# Nodino-Core2538.net
KiCad netlist of a schematic drawn in EAGLE
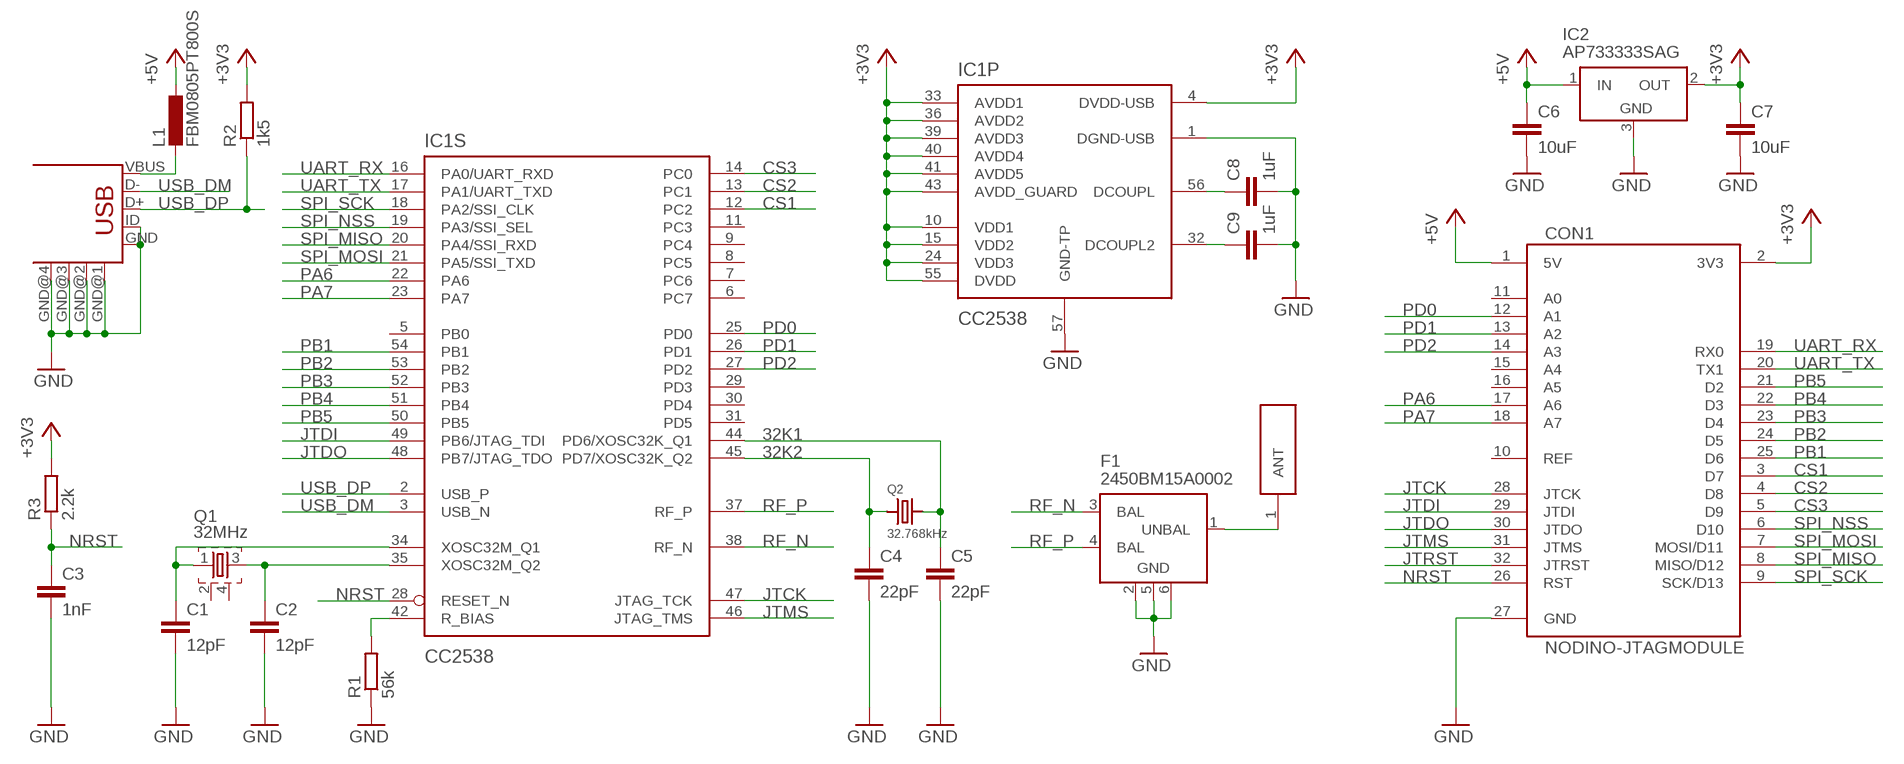
[diagram p0: schematic, sheet 1]

(export (version "E")
  (design (tool "Eeschema 10.0.6"))
  (components
    (comp (ref "ANT1")
      (value "2450AT18B100")
      (footprint "eagle-import:2450AT18B100")
      (libsource (lib "eagle-import") (part "2450AT18B100"))
    )
    (comp (ref "C1")
      (value "12pF")
      (footprint "eagle-import:C0603K")
      (libsource (lib "eagle-import") (part "C-EUC0603K"))
    )
    (comp (ref "C2")
      (value "12pF")
      (footprint "eagle-import:C0603K")
      (libsource (lib "eagle-import") (part "C-EUC0603K"))
    )
    (comp (ref "C3")
      (value "1nF")
      (footprint "eagle-import:C0603K")
      (libsource (lib "eagle-import") (part "C-EUC0603K"))
    )
    (comp (ref "C4")
      (value "22pF")
      (footprint "eagle-import:C0603K")
      (libsource (lib "eagle-import") (part "C-EUC0603K"))
    )
    (comp (ref "C5")
      (value "22pF")
      (footprint "eagle-import:C0603K")
      (libsource (lib "eagle-import") (part "C-EUC0603K"))
    )
    (comp (ref "C6")
      (value "10uF")
      (footprint "eagle-import:C0603K")
      (libsource (lib "eagle-import") (part "C-EUC0603K"))
    )
    (comp (ref "C7")
      (value "10uF")
      (footprint "eagle-import:C0603K")
      (libsource (lib "eagle-import") (part "C-EUC0603K"))
    )
    (comp (ref "C8")
      (value "1uF")
      (footprint "eagle-import:C0603K")
      (libsource (lib "eagle-import") (part "C-EUC0603K"))
    )
    (comp (ref "C9")
      (value "1uF")
      (footprint "eagle-import:C0603K")
      (libsource (lib "eagle-import") (part "C-EUC0603K"))
    )
    (comp (ref "CON1")
      (value "NODINO-JTAGMODULE")
      (footprint "eagle-import:NODINO-JTAG-MOD")
      (libsource (lib "eagle-import") (part "NODINO-JTAGMODULE"))
    )
    (comp (ref "CON2")
      (value "USB-OTG_SHIELD")
      (footprint "eagle-import:USB-UAB-S1")
      (libsource (lib "eagle-import") (part "USB-OTG_SHIELD"))
    )
    (comp (ref "F1")
      (value "2450BM15A0002")
      (footprint "eagle-import:2450BM15A0002")
      (libsource (lib "eagle-import") (part "2450BM15A0002"))
    )
    (comp (ref "IC1")
      (value "CC2538")
      (footprint "eagle-import:QFN56P800X800X100-57N")
      (libsource (lib "eagle-import") (part "CC2538"))
    )
    (comp (ref "IC2")
      (value "AP733333SAG")
      (footprint "eagle-import:SOT23")
      (libsource (lib "eagle-import") (part "AP733333SAG"))
    )
    (comp (ref "L1")
      (value "FBM0805PT800S")
      (footprint "eagle-import:L0805")
      (libsource (lib "eagle-import") (part "L-EUL0805"))
    )
    (comp (ref "Q1")
      (value "32MHz")
      (footprint "eagle-import:FA-20H")
      (libsource (lib "eagle-import") (part "FA-20H"))
    )
    (comp (ref "Q2")
      (value "32.768kHz")
      (footprint "eagle-import:ABS07")
      (libsource (lib "eagle-import") (part "CRYSTAL.ABS07"))
    )
    (comp (ref "R1")
      (value "56k")
      (footprint "eagle-import:R0603K")
      (libsource (lib "eagle-import") (part "R-EU_R0603K"))
    )
    (comp (ref "R2")
      (value "1k5")
      (footprint "eagle-import:R0603K")
      (libsource (lib "eagle-import") (part "R-EU_R0603K"))
    )
    (comp (ref "R3")
      (value "2.2k")
      (footprint "eagle-import:R0603K")
      (libsource (lib "eagle-import") (part "R-EU_R0603K"))
    )
  )
  (nets
    (net (code "1") (name "+3V3") (class "Default")
      (node (ref "C7") (pin "1") (pinfunction "1_1") (pintype "passive"))
      (node (ref "CON1") (pin "2") (pinfunction "3V3_2") (pintype "bidirectional"))
      (node (ref "IC1") (pin "10") (pinfunction "VDD1_10") (pintype "power_in"))
      (node (ref "IC1") (pin "15") (pinfunction "VDD2_15") (pintype "power_in"))
      (node (ref "IC1") (pin "24") (pinfunction "VDD3_24") (pintype "power_in"))
      (node (ref "IC1") (pin "33") (pinfunction "AVDD1_33") (pintype "power_in"))
      (node (ref "IC1") (pin "36") (pinfunction "AVDD2_36") (pintype "power_in"))
      (node (ref "IC1") (pin "39") (pinfunction "AVDD3_39") (pintype "power_in"))
      (node (ref "IC1") (pin "4") (pinfunction "DVDD-USB_4") (pintype "power_in"))
      (node (ref "IC1") (pin "40") (pinfunction "AVDD4_40") (pintype "power_in"))
      (node (ref "IC1") (pin "41") (pinfunction "AVDD5_41") (pintype "power_in"))
      (node (ref "IC1") (pin "43") (pinfunction "AVDD_GUARD_43") (pintype "power_in"))
      (node (ref "IC1") (pin "55") (pinfunction "DVDD_55") (pintype "power_in"))
      (node (ref "IC2") (pin "2") (pinfunction "OUT_2") (pintype "output"))
      (node (ref "R2") (pin "2") (pinfunction "2_2") (pintype "passive"))
      (node (ref "R3") (pin "2") (pinfunction "2_2") (pintype "passive"))
    )
    (net (code "2") (name "+5V") (class "Default")
      (node (ref "C6") (pin "1") (pinfunction "1_1") (pintype "passive"))
      (node (ref "CON1") (pin "1") (pinfunction "5V_1") (pintype "bidirectional"))
      (node (ref "IC2") (pin "1") (pinfunction "IN_1") (pintype "input"))
      (node (ref "L1") (pin "1") (pinfunction "1_1") (pintype "passive"))
    )
    (net (code "3") (name "/32K1") (class "Default")
      (node (ref "C5") (pin "1") (pinfunction "1_1") (pintype "passive"))
      (node (ref "IC1") (pin "44") (pinfunction "PD6/XOSC32K_Q1_44") (pintype "bidirectional"))
      (node (ref "Q2") (pin "2") (pinfunction "2_2") (pintype "passive"))
    )
    (net (code "4") (name "/32K2") (class "Default")
      (node (ref "C4") (pin "1") (pinfunction "1_1") (pintype "passive"))
      (node (ref "IC1") (pin "45") (pinfunction "PD7/XOSC32K_Q2_45") (pintype "bidirectional"))
      (node (ref "Q2") (pin "1") (pinfunction "1_1") (pintype "passive"))
    )
    (net (code "5") (name "/CS1") (class "Default")
      (node (ref "CON1") (pin "3") (pinfunction "D7_3") (pintype "bidirectional"))
      (node (ref "IC1") (pin "12") (pinfunction "PC2_12") (pintype "bidirectional"))
    )
    (net (code "6") (name "/CS2") (class "Default")
      (node (ref "CON1") (pin "4") (pinfunction "D8_4") (pintype "bidirectional"))
      (node (ref "IC1") (pin "13") (pinfunction "PC1_13") (pintype "bidirectional"))
    )
    (net (code "7") (name "/CS3") (class "Default")
      (node (ref "CON1") (pin "5") (pinfunction "D9_5") (pintype "bidirectional"))
      (node (ref "IC1") (pin "14") (pinfunction "PC0_14") (pintype "bidirectional"))
    )
    (net (code "8") (name "/JTCK") (class "Default")
      (node (ref "CON1") (pin "28") (pinfunction "JTCK_28") (pintype "bidirectional"))
      (node (ref "IC1") (pin "47") (pinfunction "JTAG_TCK_47") (pintype "bidirectional"))
    )
    (net (code "9") (name "/JTDI") (class "Default")
      (node (ref "CON1") (pin "29") (pinfunction "JTDI_29") (pintype "bidirectional"))
      (node (ref "IC1") (pin "49") (pinfunction "PB6/JTAG_TDI_49") (pintype "bidirectional"))
    )
    (net (code "10") (name "/JTDO") (class "Default")
      (node (ref "CON1") (pin "30") (pinfunction "JTDO_30") (pintype "bidirectional"))
      (node (ref "IC1") (pin "48") (pinfunction "PB7/JTAG_TDO_48") (pintype "bidirectional"))
    )
    (net (code "11") (name "/JTMS") (class "Default")
      (node (ref "CON1") (pin "31") (pinfunction "JTMS_31") (pintype "bidirectional"))
      (node (ref "IC1") (pin "46") (pinfunction "JTAG_TMS_46") (pintype "bidirectional"))
    )
    (net (code "12") (name "/JTRST") (class "Default")
      (node (ref "CON1") (pin "32") (pinfunction "JTRST_32") (pintype "bidirectional"))
    )
    (net (code "13") (name "/NRST") (class "Default")
      (node (ref "C3") (pin "1") (pinfunction "1_1") (pintype "passive"))
      (node (ref "CON1") (pin "26") (pinfunction "RST_26") (pintype "bidirectional"))
      (node (ref "IC1") (pin "28") (pinfunction "RESET_N_28") (pintype "input"))
      (node (ref "R3") (pin "1") (pinfunction "1_1") (pintype "passive"))
    )
    (net (code "14") (name "/PA6") (class "Default")
      (node (ref "CON1") (pin "17") (pinfunction "A6_17") (pintype "bidirectional"))
      (node (ref "IC1") (pin "22") (pinfunction "PA6_22") (pintype "bidirectional"))
    )
    (net (code "15") (name "/PA7") (class "Default")
      (node (ref "CON1") (pin "18") (pinfunction "A7_18") (pintype "bidirectional"))
      (node (ref "IC1") (pin "23") (pinfunction "PA7_23") (pintype "bidirectional"))
    )
    (net (code "16") (name "/PB1") (class "Default")
      (node (ref "CON1") (pin "25") (pinfunction "D6_25") (pintype "bidirectional"))
      (node (ref "IC1") (pin "54") (pinfunction "PB1_54") (pintype "bidirectional"))
    )
    (net (code "17") (name "/PB2") (class "Default")
      (node (ref "CON1") (pin "24") (pinfunction "D5_24") (pintype "bidirectional"))
      (node (ref "IC1") (pin "53") (pinfunction "PB2_53") (pintype "bidirectional"))
    )
    (net (code "18") (name "/PB3") (class "Default")
      (node (ref "CON1") (pin "23") (pinfunction "D4_23") (pintype "bidirectional"))
      (node (ref "IC1") (pin "52") (pinfunction "PB3_52") (pintype "bidirectional"))
    )
    (net (code "19") (name "/PB4") (class "Default")
      (node (ref "CON1") (pin "22") (pinfunction "D3_22") (pintype "bidirectional"))
      (node (ref "IC1") (pin "51") (pinfunction "PB4_51") (pintype "bidirectional"))
    )
    (net (code "20") (name "/PB5") (class "Default")
      (node (ref "CON1") (pin "21") (pinfunction "D2_21") (pintype "bidirectional"))
      (node (ref "IC1") (pin "50") (pinfunction "PB5_50") (pintype "bidirectional"))
    )
    (net (code "21") (name "/PD0") (class "Default")
      (node (ref "CON1") (pin "12") (pinfunction "A1_12") (pintype "bidirectional"))
      (node (ref "IC1") (pin "25") (pinfunction "PD0_25") (pintype "bidirectional"))
    )
    (net (code "22") (name "/PD1") (class "Default")
      (node (ref "CON1") (pin "13") (pinfunction "A2_13") (pintype "bidirectional"))
      (node (ref "IC1") (pin "26") (pinfunction "PD1_26") (pintype "bidirectional"))
    )
    (net (code "23") (name "/PD2") (class "Default")
      (node (ref "CON1") (pin "14") (pinfunction "A3_14") (pintype "bidirectional"))
      (node (ref "IC1") (pin "27") (pinfunction "PD2_27") (pintype "bidirectional"))
    )
    (net (code "24") (name "/RF_N") (class "Default")
      (node (ref "F1") (pin "3") (pinfunction "BAL_3") (pintype "passive"))
      (node (ref "IC1") (pin "38") (pinfunction "RF_N_38") (pintype "bidirectional"))
    )
    (net (code "25") (name "/RF_P") (class "Default")
      (node (ref "F1") (pin "4") (pinfunction "BAL_4") (pintype "passive"))
      (node (ref "IC1") (pin "37") (pinfunction "RF_P_37") (pintype "bidirectional"))
    )
    (net (code "26") (name "/SPI_MISO") (class "Default")
      (node (ref "CON1") (pin "8") (pinfunction "MISO/D12_8") (pintype "bidirectional"))
      (node (ref "IC1") (pin "20") (pinfunction "PA4/SSI_RXD_20") (pintype "bidirectional"))
    )
    (net (code "27") (name "/SPI_MOSI") (class "Default")
      (node (ref "CON1") (pin "7") (pinfunction "MOSI/D11_7") (pintype "bidirectional"))
      (node (ref "IC1") (pin "21") (pinfunction "PA5/SSI_TXD_21") (pintype "bidirectional"))
    )
    (net (code "28") (name "/SPI_NSS") (class "Default")
      (node (ref "CON1") (pin "6") (pinfunction "D10_6") (pintype "bidirectional"))
      (node (ref "IC1") (pin "19") (pinfunction "PA3/SSI_SEL_19") (pintype "bidirectional"))
    )
    (net (code "29") (name "/SPI_SCK") (class "Default")
      (node (ref "CON1") (pin "9") (pinfunction "SCK/D13_9") (pintype "bidirectional"))
      (node (ref "IC1") (pin "18") (pinfunction "PA2/SSI_CLK_18") (pintype "bidirectional"))
    )
    (net (code "30") (name "/UART_RX") (class "Default")
      (node (ref "CON1") (pin "19") (pinfunction "RX0_19") (pintype "bidirectional"))
      (node (ref "IC1") (pin "16") (pinfunction "PA0/UART_RXD_16") (pintype "bidirectional"))
    )
    (net (code "31") (name "/UART_TX") (class "Default")
      (node (ref "CON1") (pin "20") (pinfunction "TX1_20") (pintype "bidirectional"))
      (node (ref "IC1") (pin "17") (pinfunction "PA1/UART_TXD_17") (pintype "bidirectional"))
    )
    (net (code "32") (name "/USB_DM") (class "Default")
      (node (ref "CON2") (pin "D-") (pinfunction "D-_D-") (pintype "bidirectional"))
      (node (ref "IC1") (pin "3") (pinfunction "USB_N_3") (pintype "bidirectional"))
    )
    (net (code "33") (name "/USB_DP") (class "Default")
      (node (ref "CON2") (pin "D+") (pinfunction "D+_D+") (pintype "bidirectional"))
      (node (ref "IC1") (pin "2") (pinfunction "USB_P_2") (pintype "bidirectional"))
      (node (ref "R2") (pin "1") (pinfunction "1_1") (pintype "passive"))
    )
    (net (code "34") (name "GND") (class "Default")
      (node (ref "C1") (pin "2") (pinfunction "2_2") (pintype "passive"))
      (node (ref "C2") (pin "2") (pinfunction "2_2") (pintype "passive"))
      (node (ref "C3") (pin "2") (pinfunction "2_2") (pintype "passive"))
      (node (ref "C4") (pin "2") (pinfunction "2_2") (pintype "passive"))
      (node (ref "C5") (pin "2") (pinfunction "2_2") (pintype "passive"))
      (node (ref "C6") (pin "2") (pinfunction "2_2") (pintype "passive"))
      (node (ref "C7") (pin "2") (pinfunction "2_2") (pintype "passive"))
      (node (ref "C8") (pin "2") (pinfunction "2_2") (pintype "passive"))
      (node (ref "C9") (pin "2") (pinfunction "2_2") (pintype "passive"))
      (node (ref "CON1") (pin "27") (pinfunction "GND_27") (pintype "bidirectional"))
      (node (ref "CON2") (pin "GND") (pinfunction "GND_GND") (pintype "power_in"))
      (node (ref "CON2") (pin "GND@1") (pinfunction "GND_GND@1") (pintype "power_in"))
      (node (ref "CON2") (pin "GND@2") (pinfunction "GND_GND@2") (pintype "power_in"))
      (node (ref "CON2") (pin "GND@3") (pinfunction "GND_GND@3") (pintype "power_in"))
      (node (ref "CON2") (pin "GND@4") (pinfunction "GND_GND@4") (pintype "power_in"))
      (node (ref "CON2") (pin "ID") (pinfunction "ID_ID") (pintype "bidirectional"))
      (node (ref "F1") (pin "2") (pinfunction "GND_2") (pintype "passive"))
      (node (ref "F1") (pin "5") (pinfunction "GND_5") (pintype "passive"))
      (node (ref "F1") (pin "6") (pinfunction "GND_6") (pintype "passive"))
      (node (ref "IC1") (pin "1") (pinfunction "DGND-USB_1") (pintype "power_in"))
      (node (ref "IC1") (pin "57") (pinfunction "GND-TP_57") (pintype "power_in"))
      (node (ref "IC2") (pin "3") (pinfunction "GND_3") (pintype "power_in"))
      (node (ref "R1") (pin "1") (pinfunction "1_1") (pintype "passive"))
    )
    (net (code "35") (name "Net-(ANT1-ANT)") (class "Default")
      (node (ref "ANT1") (pin "1") (pinfunction "ANT_1") (pintype "bidirectional"))
      (node (ref "F1") (pin "1") (pinfunction "UNBAL_1") (pintype "passive"))
    )
    (net (code "36") (name "Net-(CON2-PadVBUS)") (class "Default")
      (node (ref "CON2") (pin "VBUS") (pinfunction "VBUS_VBUS") (pintype "power_in"))
      (node (ref "L1") (pin "2") (pinfunction "2_2") (pintype "passive"))
    )
    (net (code "37") (name "Net-(IC1A-DCOUPL)") (class "Default")
      (node (ref "C8") (pin "1") (pinfunction "1_1") (pintype "passive"))
      (node (ref "IC1") (pin "56") (pinfunction "DCOUPL_56") (pintype "power_in"))
    )
    (net (code "38") (name "Net-(IC1A-DCOUPL2)") (class "Default")
      (node (ref "C9") (pin "1") (pinfunction "1_1") (pintype "passive"))
      (node (ref "IC1") (pin "32") (pinfunction "DCOUPL2_32") (pintype "power_in"))
    )
    (net (code "39") (name "Net-(IC1B-R_BIAS)") (class "Default")
      (node (ref "IC1") (pin "42") (pinfunction "R_BIAS_42") (pintype "bidirectional"))
      (node (ref "R1") (pin "2") (pinfunction "2_2") (pintype "passive"))
    )
    (net (code "40") (name "Net-(IC1B-XOSC32M_Q1)") (class "Default")
      (node (ref "C1") (pin "1") (pinfunction "1_1") (pintype "passive"))
      (node (ref "IC1") (pin "34") (pinfunction "XOSC32M_Q1_34") (pintype "bidirectional"))
      (node (ref "Q1") (pin "1") (pinfunction "1_1") (pintype "passive"))
    )
    (net (code "41") (name "Net-(IC1B-XOSC32M_Q2)") (class "Default")
      (node (ref "C2") (pin "1") (pinfunction "1_1") (pintype "passive"))
      (node (ref "IC1") (pin "35") (pinfunction "XOSC32M_Q2_35") (pintype "bidirectional"))
      (node (ref "Q1") (pin "3") (pinfunction "3_3") (pintype "passive"))
    )
    (net (code "42") (name "unconnected-(CON1-A0-Pad11)") (class "Default")
      (node (ref "CON1") (pin "11") (pinfunction "A0_11") (pintype "bidirectional"))
    )
    (net (code "43") (name "unconnected-(CON1-A4-Pad15)") (class "Default")
      (node (ref "CON1") (pin "15") (pinfunction "A4_15") (pintype "bidirectional"))
    )
    (net (code "44") (name "unconnected-(CON1-A5-Pad16)") (class "Default")
      (node (ref "CON1") (pin "16") (pinfunction "A5_16") (pintype "bidirectional"))
    )
    (net (code "45") (name "unconnected-(CON1-REF-Pad10)") (class "Default")
      (node (ref "CON1") (pin "10") (pinfunction "REF_10") (pintype "bidirectional"))
    )
    (net (code "46") (name "unconnected-(IC1B-PB0-Pad5)") (class "Default")
      (node (ref "IC1") (pin "5") (pinfunction "PB0_5") (pintype "bidirectional"))
    )
    (net (code "47") (name "unconnected-(IC1B-PC3-Pad11)") (class "Default")
      (node (ref "IC1") (pin "11") (pinfunction "PC3_11") (pintype "bidirectional"))
    )
    (net (code "48") (name "unconnected-(IC1B-PC4-Pad9)") (class "Default")
      (node (ref "IC1") (pin "9") (pinfunction "PC4_9") (pintype "bidirectional"))
    )
    (net (code "49") (name "unconnected-(IC1B-PC5-Pad8)") (class "Default")
      (node (ref "IC1") (pin "8") (pinfunction "PC5_8") (pintype "bidirectional"))
    )
    (net (code "50") (name "unconnected-(IC1B-PC6-Pad7)") (class "Default")
      (node (ref "IC1") (pin "7") (pinfunction "PC6_7") (pintype "bidirectional"))
    )
    (net (code "51") (name "unconnected-(IC1B-PC7-Pad6)") (class "Default")
      (node (ref "IC1") (pin "6") (pinfunction "PC7_6") (pintype "bidirectional"))
    )
    (net (code "52") (name "unconnected-(IC1B-PD3-Pad29)") (class "Default")
      (node (ref "IC1") (pin "29") (pinfunction "PD3_29") (pintype "bidirectional"))
    )
    (net (code "53") (name "unconnected-(IC1B-PD4-Pad30)") (class "Default")
      (node (ref "IC1") (pin "30") (pinfunction "PD4_30") (pintype "bidirectional"))
    )
    (net (code "54") (name "unconnected-(IC1B-PD5-Pad31)") (class "Default")
      (node (ref "IC1") (pin "31") (pinfunction "PD5_31") (pintype "bidirectional"))
    )
    (net (code "55") (name "unconnected-(Q1-Pad2)") (class "Default")
      (node (ref "Q1") (pin "2") (pinfunction "2_2") (pintype "passive"))
    )
    (net (code "56") (name "unconnected-(Q1-Pad4)") (class "Default")
      (node (ref "Q1") (pin "4") (pinfunction "4_4") (pintype "passive"))
    )
  )
)
